# mowgli-mem.net
KiCad netlist of a schematic drawn in EAGLE
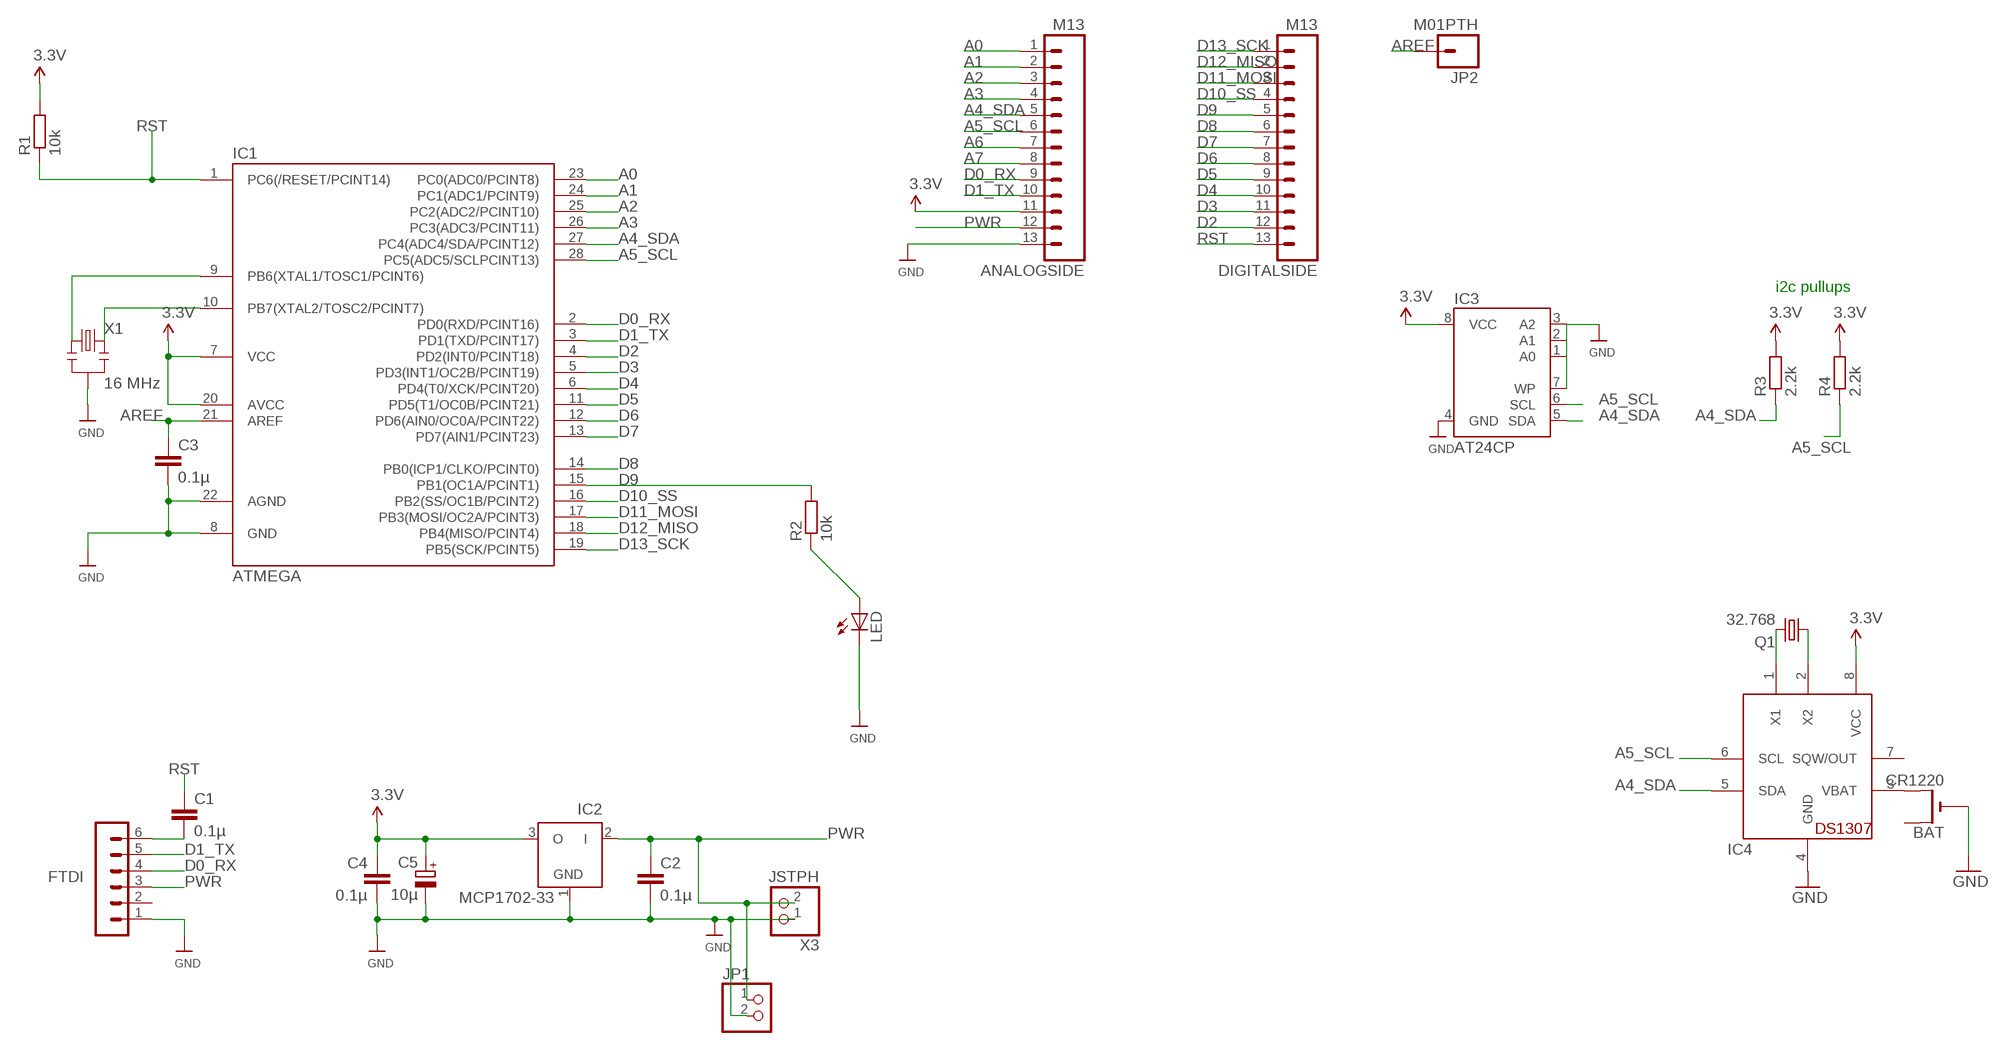
[diagram p0: schematic, sheet 1]

(export (version "E")
  (design (tool "Eeschema 10.0.6"))
  (components
    (comp (ref "ANALOGSIDE")
      (value "M13")
      (footprint "eagle-import:1X13")
      (libsource (lib "eagle-import") (part "M13"))
    )
    (comp (ref "BAT")
      (value "CR1220")
      (footprint "eagle-import:CR1220-THM")
      (libsource (lib "eagle-import") (part "CR1220THM"))
    )
    (comp (ref "C1")
      (value "0.1µ")
      (footprint "eagle-import:C025-024X044")
      (libsource (lib "eagle-import") (part "C-EU025-024X044"))
    )
    (comp (ref "C2")
      (value "0.1µ")
      (footprint "eagle-import:C025-024X044")
      (libsource (lib "eagle-import") (part "C-EU025-024X044"))
    )
    (comp (ref "C3")
      (value "0.1µ")
      (footprint "eagle-import:C025-024X044")
      (libsource (lib "eagle-import") (part "C-EU025-024X044"))
    )
    (comp (ref "C4")
      (value "0.1µ")
      (footprint "eagle-import:C025-024X044")
      (libsource (lib "eagle-import") (part "C-EU025-024X044"))
    )
    (comp (ref "C5")
      (value "10µ")
      (footprint "eagle-import:E1,8-4")
      (libsource (lib "eagle-import") (part "CPOL-EUE1.8-4"))
    )
    (comp (ref "DIGITALSIDE")
      (value "M13")
      (footprint "eagle-import:1X13")
      (libsource (lib "eagle-import") (part "M13"))
    )
    (comp (ref "FTDI")
      (value "FTDI")
      (footprint "eagle-import:MA06-1")
      (libsource (lib "eagle-import") (part "MA06-1"))
    )
    (comp (ref "IC1")
      (value "ATMEGA")
      (footprint "eagle-import:DIL28-3")
      (libsource (lib "eagle-import") (part "ATMEGA48/88/168-PU"))
    )
    (comp (ref "IC2")
      (value "MCP1702-33")
      (footprint "eagle-import:TO92")
      (libsource (lib "eagle-import") (part "MCP1702Z"))
    )
    (comp (ref "IC3")
      (value "AT24CP")
      (footprint "eagle-import:DIL08")
      (fields (field (name "MPN") "AT24C1024BW-SH-B"))
      (libsource (lib "eagle-import") (part "AT24CP"))
    )
    (comp (ref "IC4")
      (value "DS1307")
      (footprint "eagle-import:DIL08")
      (libsource (lib "eagle-import") (part "DS1307"))
    )
    (comp (ref "JP1")
      (value "PINHD-1X2")
      (footprint "eagle-import:1X02")
      (libsource (lib "eagle-import") (part "PINHD-1X2"))
    )
    (comp (ref "JP2")
      (value "M01PTH")
      (footprint "eagle-import:1X01")
      (libsource (lib "eagle-import") (part "M01PTH"))
    )
    (comp (ref "LED")
      (value "LED3MM")
      (footprint "eagle-import:LED3MM")
      (libsource (lib "eagle-import") (part "LED3MM"))
    )
    (comp (ref "Q1")
      (value "32.768")
      (footprint "eagle-import:TC38H")
      (libsource (lib "eagle-import") (part "CRYTALTC38H"))
    )
    (comp (ref "R1")
      (value "10k")
      (footprint "eagle-import:0204_7")
      (libsource (lib "eagle-import") (part "R-EU_0204/7"))
    )
    (comp (ref "R2")
      (value "10k")
      (footprint "eagle-import:0204_7")
      (libsource (lib "eagle-import") (part "R-EU_0204/7"))
    )
    (comp (ref "R3")
      (value "2.2k")
      (footprint "eagle-import:0204_7")
      (libsource (lib "eagle-import") (part "R-EU_0204/7"))
    )
    (comp (ref "R4")
      (value "2.2k")
      (footprint "eagle-import:0204_7")
      (libsource (lib "eagle-import") (part "R-EU_0204/7"))
    )
    (comp (ref "X1")
      (value "16 MHz")
      (footprint "eagle-import:RESONATOR-PTH")
      (libsource (lib "eagle-import") (part "RESONATORPTH"))
    )
    (comp (ref "X3")
      (value "JSTPH")
      (footprint "eagle-import:JSTPH2")
      (libsource (lib "eagle-import") (part "CON_JST_PH_2PIN"))
    )
  )
  (nets
    (net (code "1") (name "/A0") (class "Default")
      (node (ref "ANALOGSIDE") (pin "1") (pinfunction "1_1") (pintype "passive"))
      (node (ref "IC1") (pin "23") (pinfunction "PC0(ADC0/PCINT8)_23") (pintype "bidirectional"))
    )
    (net (code "2") (name "/A1") (class "Default")
      (node (ref "ANALOGSIDE") (pin "2") (pinfunction "2_2") (pintype "passive"))
      (node (ref "IC1") (pin "24") (pinfunction "PC1(ADC1/PCINT9)_24") (pintype "bidirectional"))
    )
    (net (code "3") (name "/A2") (class "Default")
      (node (ref "ANALOGSIDE") (pin "3") (pinfunction "3_3") (pintype "passive"))
      (node (ref "IC1") (pin "25") (pinfunction "PC2(ADC2/PCINT10)_25") (pintype "bidirectional"))
    )
    (net (code "4") (name "/A3") (class "Default")
      (node (ref "ANALOGSIDE") (pin "4") (pinfunction "4_4") (pintype "passive"))
      (node (ref "IC1") (pin "26") (pinfunction "PC3(ADC3/PCINT11)_26") (pintype "bidirectional"))
    )
    (net (code "5") (name "/A4_SDA") (class "Default")
      (node (ref "ANALOGSIDE") (pin "5") (pinfunction "5_5") (pintype "passive"))
      (node (ref "IC1") (pin "27") (pinfunction "PC4(ADC4/SDA/PCINT12)_27") (pintype "bidirectional"))
      (node (ref "IC3") (pin "5") (pinfunction "SDA_5") (pintype "bidirectional"))
      (node (ref "IC4") (pin "5") (pinfunction "SDA_5") (pintype "bidirectional"))
      (node (ref "R3") (pin "1") (pinfunction "1_1") (pintype "passive"))
    )
    (net (code "6") (name "/A5_SCL") (class "Default")
      (node (ref "ANALOGSIDE") (pin "6") (pinfunction "6_6") (pintype "passive"))
      (node (ref "IC1") (pin "28") (pinfunction "PC5(ADC5/SCLPCINT13)_28") (pintype "bidirectional"))
      (node (ref "IC3") (pin "6") (pinfunction "SCL_6") (pintype "bidirectional"))
      (node (ref "IC4") (pin "6") (pinfunction "SCL_6") (pintype "bidirectional"))
      (node (ref "R4") (pin "1") (pinfunction "1_1") (pintype "passive"))
    )
    (net (code "7") (name "/A6") (class "Default")
      (node (ref "ANALOGSIDE") (pin "7") (pinfunction "7_7") (pintype "passive"))
    )
    (net (code "8") (name "/A7") (class "Default")
      (node (ref "ANALOGSIDE") (pin "8") (pinfunction "8_8") (pintype "passive"))
    )
    (net (code "9") (name "/AREF") (class "Default")
      (node (ref "C3") (pin "1") (pinfunction "1_1") (pintype "passive"))
      (node (ref "IC1") (pin "21") (pinfunction "AREF_21") (pintype "passive"))
      (node (ref "JP2") (pin "1") (pinfunction "1_1") (pintype "passive"))
    )
    (net (code "10") (name "/D0_RX") (class "Default")
      (node (ref "ANALOGSIDE") (pin "9") (pinfunction "9_9") (pintype "passive"))
      (node (ref "FTDI") (pin "4") (pinfunction "4_4") (pintype "passive"))
      (node (ref "IC1") (pin "2") (pinfunction "PD0(RXD/PCINT16)_2") (pintype "bidirectional"))
    )
    (net (code "11") (name "/D1_TX") (class "Default")
      (node (ref "ANALOGSIDE") (pin "10") (pinfunction "10_10") (pintype "passive"))
      (node (ref "FTDI") (pin "5") (pinfunction "5_5") (pintype "passive"))
      (node (ref "IC1") (pin "3") (pinfunction "PD1(TXD/PCINT17)_3") (pintype "bidirectional"))
    )
    (net (code "12") (name "/D2") (class "Default")
      (node (ref "DIGITALSIDE") (pin "12") (pinfunction "12_12") (pintype "passive"))
      (node (ref "IC1") (pin "4") (pinfunction "PD2(INT0/PCINT18)_4") (pintype "bidirectional"))
    )
    (net (code "13") (name "/D3") (class "Default")
      (node (ref "DIGITALSIDE") (pin "11") (pinfunction "11_11") (pintype "passive"))
      (node (ref "IC1") (pin "5") (pinfunction "PD3(INT1/OC2B/PCINT19)_5") (pintype "bidirectional"))
    )
    (net (code "14") (name "/D4") (class "Default")
      (node (ref "DIGITALSIDE") (pin "10") (pinfunction "10_10") (pintype "passive"))
      (node (ref "IC1") (pin "6") (pinfunction "PD4(T0/XCK/PCINT20)_6") (pintype "bidirectional"))
    )
    (net (code "15") (name "/D5") (class "Default")
      (node (ref "DIGITALSIDE") (pin "9") (pinfunction "9_9") (pintype "passive"))
      (node (ref "IC1") (pin "11") (pinfunction "PD5(T1/OC0B/PCINT21)_11") (pintype "bidirectional"))
    )
    (net (code "16") (name "/D6") (class "Default")
      (node (ref "DIGITALSIDE") (pin "8") (pinfunction "8_8") (pintype "passive"))
      (node (ref "IC1") (pin "12") (pinfunction "PD6(AIN0/OC0A/PCINT22)_12") (pintype "bidirectional"))
    )
    (net (code "17") (name "/D7") (class "Default")
      (node (ref "DIGITALSIDE") (pin "7") (pinfunction "7_7") (pintype "passive"))
      (node (ref "IC1") (pin "13") (pinfunction "PD7(AIN1/PCINT23)_13") (pintype "bidirectional"))
    )
    (net (code "18") (name "/D8") (class "Default")
      (node (ref "DIGITALSIDE") (pin "6") (pinfunction "6_6") (pintype "passive"))
      (node (ref "IC1") (pin "14") (pinfunction "PB0(ICP1/CLKO/PCINT0)_14") (pintype "bidirectional"))
    )
    (net (code "19") (name "/D9") (class "Default")
      (node (ref "DIGITALSIDE") (pin "5") (pinfunction "5_5") (pintype "passive"))
      (node (ref "IC1") (pin "15") (pinfunction "PB1(OC1A/PCINT1)_15") (pintype "bidirectional"))
      (node (ref "R2") (pin "2") (pinfunction "2_2") (pintype "passive"))
    )
    (net (code "20") (name "/D10_SS") (class "Default")
      (node (ref "DIGITALSIDE") (pin "4") (pinfunction "4_4") (pintype "passive"))
      (node (ref "IC1") (pin "16") (pinfunction "PB2(SS/OC1B/PCINT2)_16") (pintype "bidirectional"))
    )
    (net (code "21") (name "/D11_MOSI") (class "Default")
      (node (ref "DIGITALSIDE") (pin "3") (pinfunction "3_3") (pintype "passive"))
      (node (ref "IC1") (pin "17") (pinfunction "PB3(MOSI/OC2A/PCINT3)_17") (pintype "bidirectional"))
    )
    (net (code "22") (name "/D12_MISO") (class "Default")
      (node (ref "DIGITALSIDE") (pin "2") (pinfunction "2_2") (pintype "passive"))
      (node (ref "IC1") (pin "18") (pinfunction "PB4(MISO/PCINT4)_18") (pintype "bidirectional"))
    )
    (net (code "23") (name "/D13_SCK") (class "Default")
      (node (ref "DIGITALSIDE") (pin "1") (pinfunction "1_1") (pintype "passive"))
      (node (ref "IC1") (pin "19") (pinfunction "PB5(SCK/PCINT5)_19") (pintype "bidirectional"))
    )
    (net (code "24") (name "/PWR") (class "Default")
      (node (ref "ANALOGSIDE") (pin "12") (pinfunction "12_12") (pintype "passive"))
      (node (ref "C2") (pin "1") (pinfunction "1_1") (pintype "passive"))
      (node (ref "FTDI") (pin "3") (pinfunction "3_3") (pintype "passive"))
      (node (ref "IC2") (pin "2") (pinfunction "I_2") (pintype "input"))
      (node (ref "JP1") (pin "1") (pinfunction "1_1") (pintype "passive"))
      (node (ref "X3") (pin "2") (pinfunction "2_2") (pintype "passive"))
    )
    (net (code "25") (name "/RST") (class "Default")
      (node (ref "C1") (pin "1") (pinfunction "1_1") (pintype "passive"))
      (node (ref "DIGITALSIDE") (pin "13") (pinfunction "13_13") (pintype "passive"))
      (node (ref "IC1") (pin "1") (pinfunction "PC6(/RESET/PCINT14)_1") (pintype "bidirectional"))
      (node (ref "R1") (pin "1") (pinfunction "1_1") (pintype "passive"))
    )
    (net (code "26") (name "3.3V") (class "Default")
      (node (ref "ANALOGSIDE") (pin "11") (pinfunction "11_11") (pintype "passive"))
      (node (ref "C4") (pin "1") (pinfunction "1_1") (pintype "passive"))
      (node (ref "C5") (pin "+") (pinfunction "+_+") (pintype "passive"))
      (node (ref "IC1") (pin "20") (pinfunction "AVCC_20") (pintype "passive"))
      (node (ref "IC1") (pin "7") (pinfunction "VCC_7") (pintype "power_in"))
      (node (ref "IC2") (pin "3") (pinfunction "O_3") (pintype "input"))
      (node (ref "IC3") (pin "8") (pinfunction "VCC_8") (pintype "power_in"))
      (node (ref "IC4") (pin "8") (pinfunction "VCC_8") (pintype "power_in"))
      (node (ref "R1") (pin "2") (pinfunction "2_2") (pintype "passive"))
      (node (ref "R3") (pin "2") (pinfunction "2_2") (pintype "passive"))
      (node (ref "R4") (pin "2") (pinfunction "2_2") (pintype "passive"))
    )
    (net (code "27") (name "GND") (class "Default")
      (node (ref "ANALOGSIDE") (pin "13") (pinfunction "13_13") (pintype "passive"))
      (node (ref "BAT") (pin "-") (pinfunction "-_-") (pintype "passive"))
      (node (ref "C2") (pin "2") (pinfunction "2_2") (pintype "passive"))
      (node (ref "C3") (pin "2") (pinfunction "2_2") (pintype "passive"))
      (node (ref "C4") (pin "2") (pinfunction "2_2") (pintype "passive"))
      (node (ref "C5") (pin "-") (pinfunction "-_-") (pintype "passive"))
      (node (ref "FTDI") (pin "1") (pinfunction "1_1") (pintype "passive"))
      (node (ref "IC1") (pin "22") (pinfunction "AGND_22") (pintype "power_in"))
      (node (ref "IC1") (pin "8") (pinfunction "GND_8") (pintype "power_in"))
      (node (ref "IC2") (pin "1") (pinfunction "GND_1") (pintype "power_in"))
      (node (ref "IC3") (pin "1") (pinfunction "A0_1") (pintype "input"))
      (node (ref "IC3") (pin "2") (pinfunction "A1_2") (pintype "input"))
      (node (ref "IC3") (pin "3") (pinfunction "A2_3") (pintype "input"))
      (node (ref "IC3") (pin "4") (pinfunction "GND_4") (pintype "power_in"))
      (node (ref "IC3") (pin "7") (pinfunction "WP_7") (pintype "input"))
      (node (ref "IC4") (pin "4") (pinfunction "GND_4") (pintype "power_in"))
      (node (ref "JP1") (pin "2") (pinfunction "2_2") (pintype "passive"))
      (node (ref "LED") (pin "K") (pinfunction "C_K") (pintype "passive"))
      (node (ref "X1") (pin "2") (pinfunction "2_2") (pintype "passive"))
      (node (ref "X3") (pin "1") (pinfunction "1_1") (pintype "passive"))
    )
    (net (code "28") (name "Net-(BAT-+1)") (class "Default")
      (node (ref "BAT") (pin "+2") (pinfunction "+1_+2") (pintype "passive"))
      (node (ref "IC4") (pin "3") (pinfunction "VBAT_3") (pintype "power_in"))
    )
    (net (code "29") (name "Net-(C1-Pad2)") (class "Default")
      (node (ref "C1") (pin "2") (pinfunction "2_2") (pintype "passive"))
      (node (ref "FTDI") (pin "6") (pinfunction "6_6") (pintype "passive"))
    )
    (net (code "30") (name "Net-(IC1-PB6(XTAL1{slash}TOSC1{slash}PCINT6))") (class "Default")
      (node (ref "IC1") (pin "9") (pinfunction "PB6(XTAL1/TOSC1/PCINT6)_9") (pintype "bidirectional"))
      (node (ref "X1") (pin "1") (pinfunction "1_1") (pintype "passive"))
    )
    (net (code "31") (name "Net-(IC1-PB7(XTAL2{slash}TOSC2{slash}PCINT7))") (class "Default")
      (node (ref "IC1") (pin "10") (pinfunction "PB7(XTAL2/TOSC2/PCINT7)_10") (pintype "bidirectional"))
      (node (ref "X1") (pin "3") (pinfunction "3_3") (pintype "passive"))
    )
    (net (code "32") (name "Net-(IC4-X1)") (class "Default")
      (node (ref "IC4") (pin "1") (pinfunction "X1_1") (pintype "passive"))
      (node (ref "Q1") (pin "2") (pinfunction "2_2") (pintype "passive"))
    )
    (net (code "33") (name "Net-(IC4-X2)") (class "Default")
      (node (ref "IC4") (pin "2") (pinfunction "X2_2") (pintype "passive"))
      (node (ref "Q1") (pin "1") (pinfunction "1_1") (pintype "passive"))
    )
    (net (code "34") (name "Net-(LED-PadA)") (class "Default")
      (node (ref "LED") (pin "A") (pinfunction "A_A") (pintype "passive"))
      (node (ref "R2") (pin "1") (pinfunction "1_1") (pintype "passive"))
    )
    (net (code "35") (name "unconnected-(BAT-+-Pad+1)") (class "Default")
      (node (ref "BAT") (pin "+1") (pinfunction "+_+1") (pintype "passive"))
    )
    (net (code "36") (name "unconnected-(FTDI-Pad2)") (class "Default")
      (node (ref "FTDI") (pin "2") (pinfunction "2_2") (pintype "passive"))
    )
    (net (code "37") (name "unconnected-(IC4-SQW{slash}OUT-Pad7)") (class "Default")
      (node (ref "IC4") (pin "7") (pinfunction "SQW/OUT_7") (pintype "bidirectional"))
    )
  )
)
